# v6566_v1.net
KiCad netlist of a schematic drawn in EAGLE
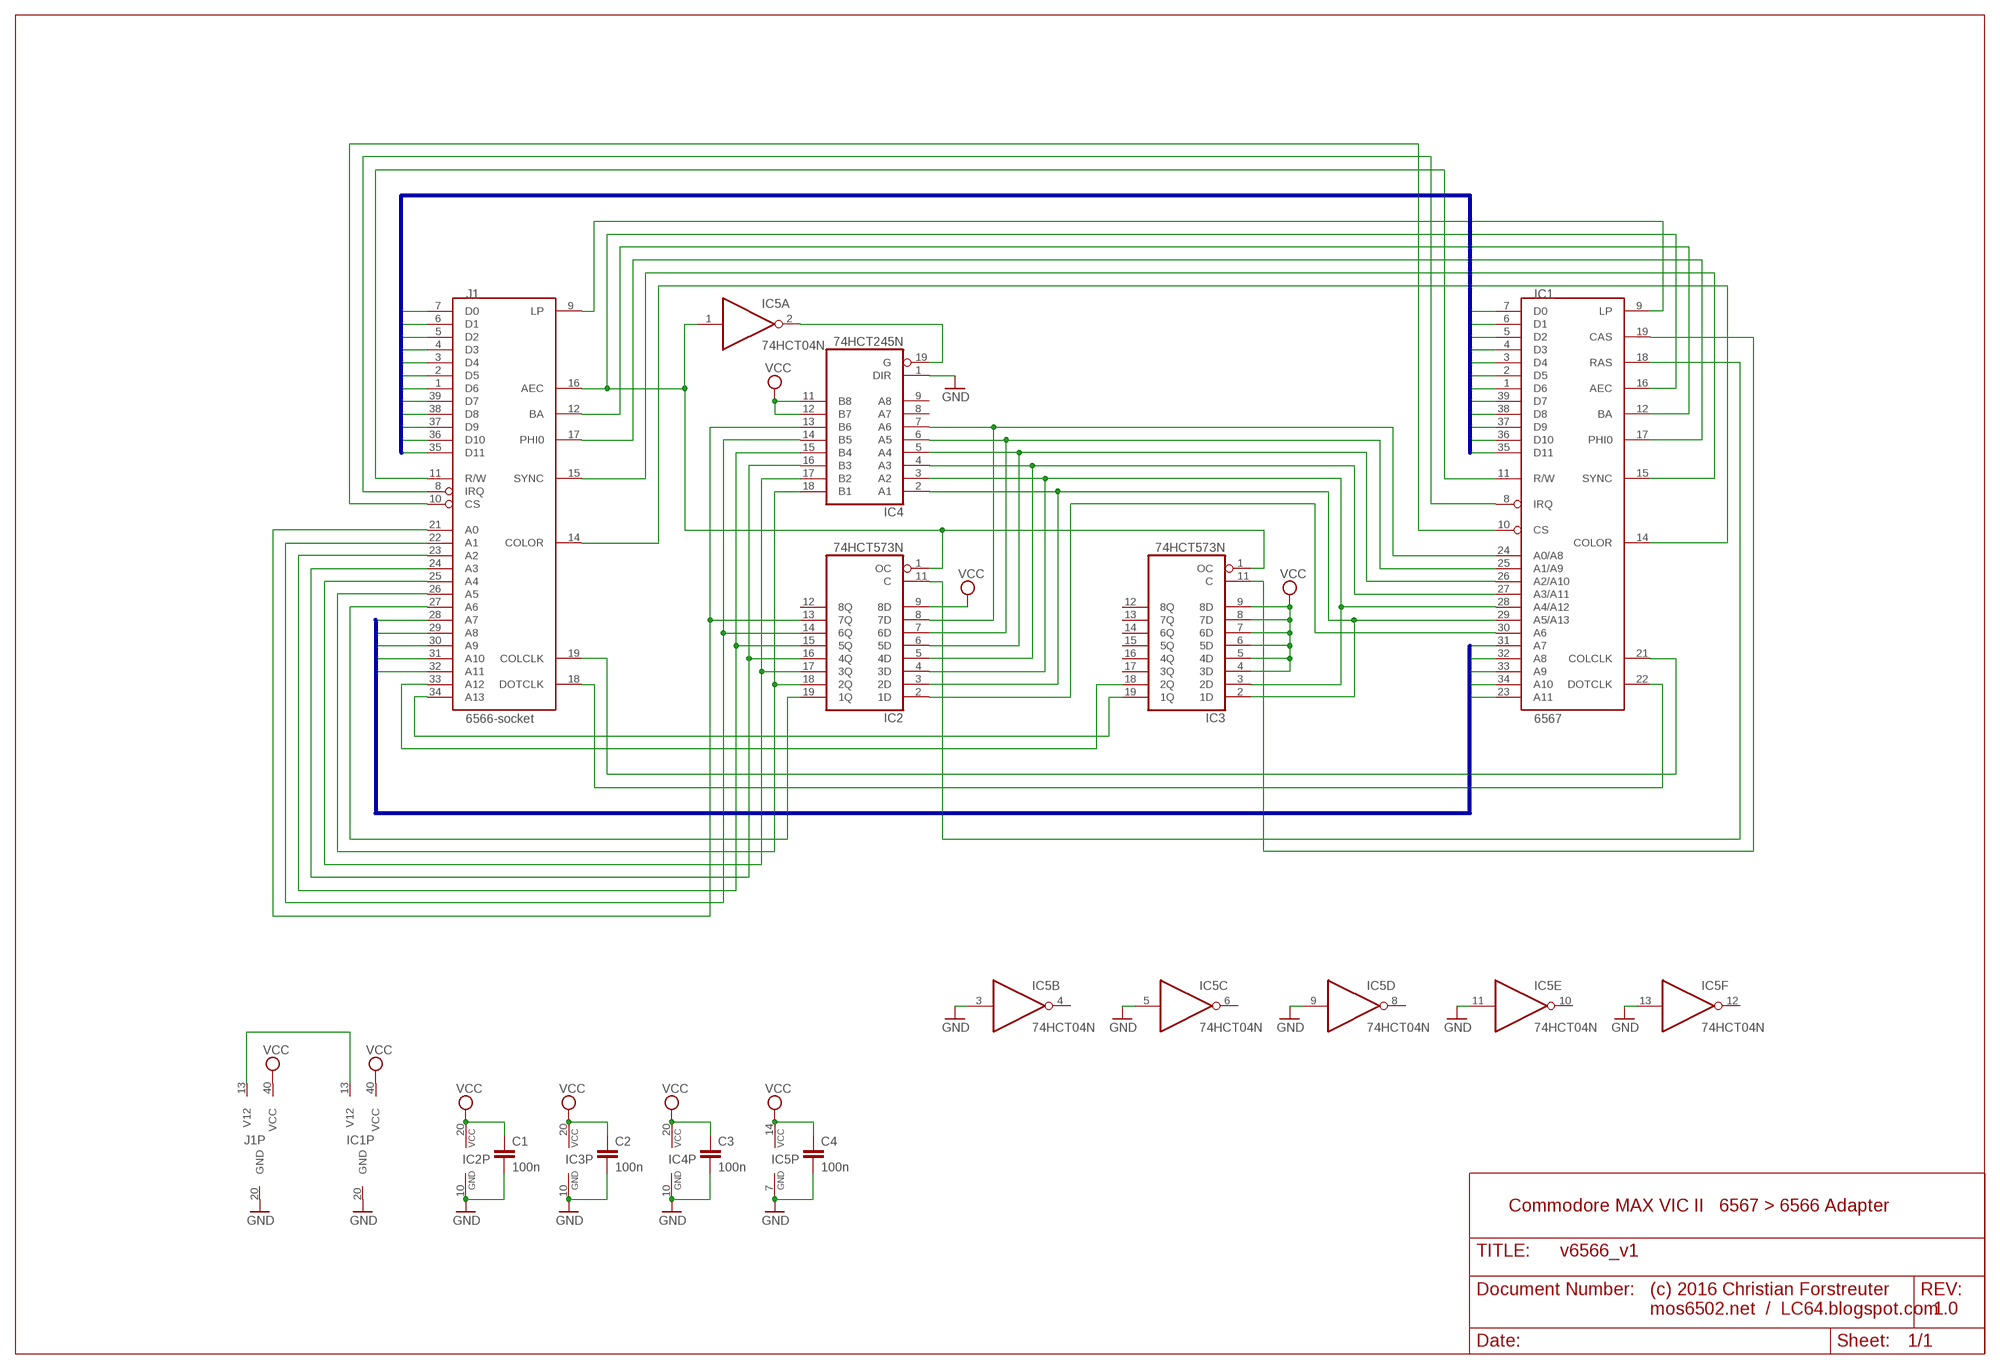
[diagram p0: schematic, sheet 1]

(export (version "E")
  (design (tool "Eeschema 10.0.6"))
  (components
    (comp (ref "C1")
      (value "100n")
      (footprint "eagle-import:_C5MM")
      (libsource (lib "eagle-import") (part "C_CERAMIC_5MM"))
    )
    (comp (ref "C2")
      (value "100n")
      (footprint "eagle-import:_C5MM")
      (libsource (lib "eagle-import") (part "C_CERAMIC_5MM"))
    )
    (comp (ref "C3")
      (value "100n")
      (footprint "eagle-import:_C5MM")
      (libsource (lib "eagle-import") (part "C_CERAMIC_5MM"))
    )
    (comp (ref "C4")
      (value "100n")
      (footprint "eagle-import:_C5MM")
      (libsource (lib "eagle-import") (part "C_CERAMIC_5MM"))
    )
    (comp (ref "IC1")
      (value "6567")
      (footprint "eagle-import:DIP40")
      (libsource (lib "eagle-import") (part "6569"))
    )
    (comp (ref "IC2")
      (value "74HCT573N")
      (footprint "eagle-import:DIL20")
      (libsource (lib "eagle-import") (part "74573NHCT"))
    )
    (comp (ref "IC3")
      (value "74HCT573N")
      (footprint "eagle-import:DIL20")
      (libsource (lib "eagle-import") (part "74573NHCT"))
    )
    (comp (ref "IC4")
      (value "74HCT245N")
      (footprint "eagle-import:DIL20")
      (libsource (lib "eagle-import") (part "74245NHCT"))
    )
    (comp (ref "IC5")
      (value "74HCT04N")
      (footprint "eagle-import:DIL14")
      (libsource (lib "eagle-import") (part "7404NHCT"))
    )
    (comp (ref "J1")
      (value "6566-socket")
      (footprint "eagle-import:DIP40")
      (libsource (lib "eagle-import") (part "6566"))
    )
  )
  (nets
    (net (code "1") (name "/A7") (class "Default")
      (node (ref "IC1") (pin "31") (pinfunction "A7_31") (pintype "bidirectional"))
      (node (ref "J1") (pin "28") (pinfunction "A7_28") (pintype "bidirectional"))
    )
    (net (code "2") (name "/A8") (class "Default")
      (node (ref "IC1") (pin "32") (pinfunction "A8_32") (pintype "input"))
      (node (ref "J1") (pin "29") (pinfunction "A8_29") (pintype "input"))
    )
    (net (code "3") (name "/A9") (class "Default")
      (node (ref "IC1") (pin "33") (pinfunction "A9_33") (pintype "input"))
      (node (ref "J1") (pin "30") (pinfunction "A9_30") (pintype "input"))
    )
    (net (code "4") (name "/A10") (class "Default")
      (node (ref "IC1") (pin "34") (pinfunction "A10_34") (pintype "input"))
      (node (ref "J1") (pin "31") (pinfunction "A10_31") (pintype "input"))
    )
    (net (code "5") (name "/A11") (class "Default")
      (node (ref "IC1") (pin "23") (pinfunction "A11_23") (pintype "input"))
      (node (ref "J1") (pin "32") (pinfunction "A11_32") (pintype "input"))
    )
    (net (code "6") (name "/D0") (class "Default")
      (node (ref "IC1") (pin "7") (pinfunction "D0_7") (pintype "tri_state"))
      (node (ref "J1") (pin "7") (pinfunction "D0_7") (pintype "tri_state"))
    )
    (net (code "7") (name "/D1") (class "Default")
      (node (ref "IC1") (pin "6") (pinfunction "D1_6") (pintype "tri_state"))
      (node (ref "J1") (pin "6") (pinfunction "D1_6") (pintype "tri_state"))
    )
    (net (code "8") (name "/D2") (class "Default")
      (node (ref "IC1") (pin "5") (pinfunction "D2_5") (pintype "tri_state"))
      (node (ref "J1") (pin "5") (pinfunction "D2_5") (pintype "tri_state"))
    )
    (net (code "9") (name "/D3") (class "Default")
      (node (ref "IC1") (pin "4") (pinfunction "D3_4") (pintype "tri_state"))
      (node (ref "J1") (pin "4") (pinfunction "D3_4") (pintype "tri_state"))
    )
    (net (code "10") (name "/D4") (class "Default")
      (node (ref "IC1") (pin "3") (pinfunction "D4_3") (pintype "tri_state"))
      (node (ref "J1") (pin "3") (pinfunction "D4_3") (pintype "tri_state"))
    )
    (net (code "11") (name "/D5") (class "Default")
      (node (ref "IC1") (pin "2") (pinfunction "D5_2") (pintype "tri_state"))
      (node (ref "J1") (pin "2") (pinfunction "D5_2") (pintype "tri_state"))
    )
    (net (code "12") (name "/D6") (class "Default")
      (node (ref "IC1") (pin "1") (pinfunction "D6_1") (pintype "tri_state"))
      (node (ref "J1") (pin "1") (pinfunction "D6_1") (pintype "tri_state"))
    )
    (net (code "13") (name "/D7") (class "Default")
      (node (ref "IC1") (pin "39") (pinfunction "D7_39") (pintype "tri_state"))
      (node (ref "J1") (pin "39") (pinfunction "D7_39") (pintype "tri_state"))
    )
    (net (code "14") (name "/D8") (class "Default")
      (node (ref "IC1") (pin "38") (pinfunction "D8_38") (pintype "tri_state"))
      (node (ref "J1") (pin "38") (pinfunction "D8_38") (pintype "tri_state"))
    )
    (net (code "15") (name "/D9") (class "Default")
      (node (ref "IC1") (pin "37") (pinfunction "D9_37") (pintype "tri_state"))
      (node (ref "J1") (pin "37") (pinfunction "D9_37") (pintype "tri_state"))
    )
    (net (code "16") (name "/D10") (class "Default")
      (node (ref "IC1") (pin "36") (pinfunction "D10_36") (pintype "tri_state"))
      (node (ref "J1") (pin "36") (pinfunction "D10_36") (pintype "tri_state"))
    )
    (net (code "17") (name "/D11") (class "Default")
      (node (ref "IC1") (pin "35") (pinfunction "D11_35") (pintype "tri_state"))
      (node (ref "J1") (pin "35") (pinfunction "D11_35") (pintype "tri_state"))
    )
    (net (code "18") (name "GND") (class "Default")
      (node (ref "C1") (pin "2") (pinfunction "2_2") (pintype "passive"))
      (node (ref "C2") (pin "2") (pinfunction "2_2") (pintype "passive"))
      (node (ref "C3") (pin "2") (pinfunction "2_2") (pintype "passive"))
      (node (ref "C4") (pin "2") (pinfunction "2_2") (pintype "passive"))
      (node (ref "IC1") (pin "20") (pinfunction "GND_20") (pintype "power_in"))
      (node (ref "IC2") (pin "10") (pinfunction "GND_10") (pintype "power_in"))
      (node (ref "IC3") (pin "10") (pinfunction "GND_10") (pintype "power_in"))
      (node (ref "IC4") (pin "1") (pinfunction "DIR_1") (pintype "input"))
      (node (ref "IC4") (pin "10") (pinfunction "GND_10") (pintype "power_in"))
      (node (ref "IC5") (pin "11") (pinfunction "I_11") (pintype "input"))
      (node (ref "IC5") (pin "13") (pinfunction "I_13") (pintype "input"))
      (node (ref "IC5") (pin "3") (pinfunction "I_3") (pintype "input"))
      (node (ref "IC5") (pin "5") (pinfunction "I_5") (pintype "input"))
      (node (ref "IC5") (pin "7") (pinfunction "GND_7") (pintype "power_in"))
      (node (ref "IC5") (pin "9") (pinfunction "I_9") (pintype "input"))
      (node (ref "J1") (pin "20") (pinfunction "GND_20") (pintype "power_in"))
    )
    (net (code "19") (name "Net-(IC1A-A0{slash}A8)") (class "Default")
      (node (ref "IC1") (pin "24") (pinfunction "A0/A8_24") (pintype "bidirectional"))
      (node (ref "IC2") (pin "8") (pinfunction "7D_8") (pintype "input"))
      (node (ref "IC4") (pin "7") (pinfunction "A6_7") (pintype "bidirectional"))
    )
    (net (code "20") (name "Net-(IC1A-A1{slash}A9)") (class "Default")
      (node (ref "IC1") (pin "25") (pinfunction "A1/A9_25") (pintype "bidirectional"))
      (node (ref "IC2") (pin "7") (pinfunction "6D_7") (pintype "input"))
      (node (ref "IC4") (pin "6") (pinfunction "A5_6") (pintype "bidirectional"))
    )
    (net (code "21") (name "Net-(IC1A-A2{slash}A10)") (class "Default")
      (node (ref "IC1") (pin "26") (pinfunction "A2/A10_26") (pintype "bidirectional"))
      (node (ref "IC2") (pin "6") (pinfunction "5D_6") (pintype "input"))
      (node (ref "IC4") (pin "5") (pinfunction "A4_5") (pintype "bidirectional"))
    )
    (net (code "22") (name "Net-(IC1A-A3{slash}A11)") (class "Default")
      (node (ref "IC1") (pin "27") (pinfunction "A3/A11_27") (pintype "bidirectional"))
      (node (ref "IC2") (pin "5") (pinfunction "4D_5") (pintype "input"))
      (node (ref "IC4") (pin "4") (pinfunction "A3_4") (pintype "bidirectional"))
    )
    (net (code "23") (name "Net-(IC1A-A4{slash}A12)") (class "Default")
      (node (ref "IC1") (pin "28") (pinfunction "A4/A12_28") (pintype "bidirectional"))
      (node (ref "IC2") (pin "4") (pinfunction "3D_4") (pintype "input"))
      (node (ref "IC3") (pin "3") (pinfunction "2D_3") (pintype "input"))
      (node (ref "IC4") (pin "3") (pinfunction "A2_3") (pintype "bidirectional"))
    )
    (net (code "24") (name "Net-(IC1A-A5{slash}A13)") (class "Default")
      (node (ref "IC1") (pin "29") (pinfunction "A5/A13_29") (pintype "bidirectional"))
      (node (ref "IC2") (pin "3") (pinfunction "2D_3") (pintype "input"))
      (node (ref "IC3") (pin "2") (pinfunction "1D_2") (pintype "input"))
      (node (ref "IC4") (pin "2") (pinfunction "A1_2") (pintype "bidirectional"))
    )
    (net (code "25") (name "Net-(IC1A-A6)") (class "Default")
      (node (ref "IC1") (pin "30") (pinfunction "A6_30") (pintype "bidirectional"))
      (node (ref "IC2") (pin "2") (pinfunction "1D_2") (pintype "input"))
    )
    (net (code "26") (name "Net-(IC1A-AEC)") (class "Default")
      (node (ref "IC1") (pin "16") (pinfunction "AEC_16") (pintype "output"))
      (node (ref "IC2") (pin "1") (pinfunction "OC_1") (pintype "input"))
      (node (ref "IC3") (pin "1") (pinfunction "OC_1") (pintype "input"))
      (node (ref "IC5") (pin "1") (pinfunction "I_1") (pintype "input"))
      (node (ref "J1") (pin "16") (pinfunction "AEC_16") (pintype "output"))
    )
    (net (code "27") (name "Net-(IC1A-BA)") (class "Default")
      (node (ref "IC1") (pin "12") (pinfunction "BA_12") (pintype "output"))
      (node (ref "J1") (pin "12") (pinfunction "BA_12") (pintype "output"))
    )
    (net (code "28") (name "Net-(IC1A-CAS)") (class "Default")
      (node (ref "IC1") (pin "19") (pinfunction "CAS_19") (pintype "output"))
      (node (ref "IC3") (pin "11") (pinfunction "C_11") (pintype "input"))
    )
    (net (code "29") (name "Net-(IC1A-COLCLK)") (class "Default")
      (node (ref "IC1") (pin "21") (pinfunction "COLCLK_21") (pintype "input"))
      (node (ref "J1") (pin "19") (pinfunction "COLCLK_19") (pintype "input"))
    )
    (net (code "30") (name "Net-(IC1A-COLOR)") (class "Default")
      (node (ref "IC1") (pin "14") (pinfunction "COLOR_14") (pintype "output"))
      (node (ref "J1") (pin "14") (pinfunction "COLOR_14") (pintype "output"))
    )
    (net (code "31") (name "Net-(IC1A-CS)") (class "Default")
      (node (ref "IC1") (pin "10") (pinfunction "CS_10") (pintype "input"))
      (node (ref "J1") (pin "10") (pinfunction "CS_10") (pintype "input"))
    )
    (net (code "32") (name "Net-(IC1A-DOTCLK)") (class "Default")
      (node (ref "IC1") (pin "22") (pinfunction "DOTCLK_22") (pintype "input"))
      (node (ref "J1") (pin "18") (pinfunction "DOTCLK_18") (pintype "input"))
    )
    (net (code "33") (name "Net-(IC1A-IRQ)") (class "Default")
      (node (ref "IC1") (pin "8") (pinfunction "IRQ_8") (pintype "open_collector"))
      (node (ref "J1") (pin "8") (pinfunction "IRQ_8") (pintype "open_collector"))
    )
    (net (code "34") (name "Net-(IC1A-LP)") (class "Default")
      (node (ref "IC1") (pin "9") (pinfunction "LP_9") (pintype "input"))
      (node (ref "J1") (pin "9") (pinfunction "LP_9") (pintype "input"))
    )
    (net (code "35") (name "Net-(IC1A-PHI0)") (class "Default")
      (node (ref "IC1") (pin "17") (pinfunction "PHI0_17") (pintype "output"))
      (node (ref "J1") (pin "17") (pinfunction "PHI0_17") (pintype "output"))
    )
    (net (code "36") (name "Net-(IC1A-RAS)") (class "Default")
      (node (ref "IC1") (pin "18") (pinfunction "RAS_18") (pintype "output"))
      (node (ref "IC2") (pin "11") (pinfunction "C_11") (pintype "input"))
    )
    (net (code "37") (name "Net-(IC1A-R{slash}W)") (class "Default")
      (node (ref "IC1") (pin "11") (pinfunction "R/W_11") (pintype "input"))
      (node (ref "J1") (pin "11") (pinfunction "R/W_11") (pintype "input"))
    )
    (net (code "38") (name "Net-(IC1A-SYNC)") (class "Default")
      (node (ref "IC1") (pin "15") (pinfunction "SYNC_15") (pintype "output"))
      (node (ref "J1") (pin "15") (pinfunction "SYNC_15") (pintype "output"))
    )
    (net (code "39") (name "Net-(IC1B-V12)") (class "Default")
      (node (ref "IC1") (pin "13") (pinfunction "V12_13") (pintype "power_in"))
      (node (ref "J1") (pin "13") (pinfunction "V12_13") (pintype "power_in"))
    )
    (net (code "40") (name "Net-(IC2A-1Q)") (class "Default")
      (node (ref "IC2") (pin "19") (pinfunction "1Q_19") (pintype "tri_state"))
      (node (ref "J1") (pin "27") (pinfunction "A6_27") (pintype "bidirectional"))
    )
    (net (code "41") (name "Net-(IC2A-2Q)") (class "Default")
      (node (ref "IC2") (pin "18") (pinfunction "2Q_18") (pintype "tri_state"))
      (node (ref "IC4") (pin "18") (pinfunction "B1_18") (pintype "bidirectional"))
      (node (ref "J1") (pin "26") (pinfunction "A5_26") (pintype "bidirectional"))
    )
    (net (code "42") (name "Net-(IC2A-3Q)") (class "Default")
      (node (ref "IC2") (pin "17") (pinfunction "3Q_17") (pintype "tri_state"))
      (node (ref "IC4") (pin "17") (pinfunction "B2_17") (pintype "bidirectional"))
      (node (ref "J1") (pin "25") (pinfunction "A4_25") (pintype "bidirectional"))
    )
    (net (code "43") (name "Net-(IC2A-4Q)") (class "Default")
      (node (ref "IC2") (pin "16") (pinfunction "4Q_16") (pintype "tri_state"))
      (node (ref "IC4") (pin "16") (pinfunction "B3_16") (pintype "bidirectional"))
      (node (ref "J1") (pin "24") (pinfunction "A3_24") (pintype "bidirectional"))
    )
    (net (code "44") (name "Net-(IC2A-5Q)") (class "Default")
      (node (ref "IC2") (pin "15") (pinfunction "5Q_15") (pintype "tri_state"))
      (node (ref "IC4") (pin "15") (pinfunction "B4_15") (pintype "bidirectional"))
      (node (ref "J1") (pin "23") (pinfunction "A2_23") (pintype "bidirectional"))
    )
    (net (code "45") (name "Net-(IC2A-6Q)") (class "Default")
      (node (ref "IC2") (pin "14") (pinfunction "6Q_14") (pintype "tri_state"))
      (node (ref "IC4") (pin "14") (pinfunction "B5_14") (pintype "bidirectional"))
      (node (ref "J1") (pin "22") (pinfunction "A1_22") (pintype "bidirectional"))
    )
    (net (code "46") (name "Net-(IC2A-7Q)") (class "Default")
      (node (ref "IC2") (pin "13") (pinfunction "7Q_13") (pintype "tri_state"))
      (node (ref "IC4") (pin "13") (pinfunction "B6_13") (pintype "bidirectional"))
      (node (ref "J1") (pin "21") (pinfunction "A0_21") (pintype "bidirectional"))
    )
    (net (code "47") (name "Net-(IC3A-1Q)") (class "Default")
      (node (ref "IC3") (pin "19") (pinfunction "1Q_19") (pintype "tri_state"))
      (node (ref "J1") (pin "34") (pinfunction "A13_34") (pintype "input"))
    )
    (net (code "48") (name "Net-(IC3A-2Q)") (class "Default")
      (node (ref "IC3") (pin "18") (pinfunction "2Q_18") (pintype "tri_state"))
      (node (ref "J1") (pin "33") (pinfunction "A12_33") (pintype "input"))
    )
    (net (code "49") (name "Net-(IC4A-G)") (class "Default")
      (node (ref "IC4") (pin "19") (pinfunction "G_19") (pintype "input"))
      (node (ref "IC5") (pin "2") (pinfunction "O_2") (pintype "output"))
    )
    (net (code "50") (name "VCC") (class "Default")
      (node (ref "C1") (pin "1") (pinfunction "1_1") (pintype "passive"))
      (node (ref "C2") (pin "1") (pinfunction "1_1") (pintype "passive"))
      (node (ref "C3") (pin "1") (pinfunction "1_1") (pintype "passive"))
      (node (ref "C4") (pin "1") (pinfunction "1_1") (pintype "passive"))
      (node (ref "IC1") (pin "40") (pinfunction "VCC_40") (pintype "power_in"))
      (node (ref "IC2") (pin "20") (pinfunction "VCC_20") (pintype "power_in"))
      (node (ref "IC2") (pin "9") (pinfunction "8D_9") (pintype "input"))
      (node (ref "IC3") (pin "20") (pinfunction "VCC_20") (pintype "power_in"))
      (node (ref "IC3") (pin "4") (pinfunction "3D_4") (pintype "input"))
      (node (ref "IC3") (pin "5") (pinfunction "4D_5") (pintype "input"))
      (node (ref "IC3") (pin "6") (pinfunction "5D_6") (pintype "input"))
      (node (ref "IC3") (pin "7") (pinfunction "6D_7") (pintype "input"))
      (node (ref "IC3") (pin "8") (pinfunction "7D_8") (pintype "input"))
      (node (ref "IC3") (pin "9") (pinfunction "8D_9") (pintype "input"))
      (node (ref "IC4") (pin "11") (pinfunction "B8_11") (pintype "bidirectional"))
      (node (ref "IC4") (pin "12") (pinfunction "B7_12") (pintype "bidirectional"))
      (node (ref "IC4") (pin "20") (pinfunction "VCC_20") (pintype "power_in"))
      (node (ref "IC5") (pin "14") (pinfunction "VCC_14") (pintype "power_in"))
      (node (ref "J1") (pin "40") (pinfunction "VCC_40") (pintype "power_in"))
    )
    (net (code "51") (name "unconnected-(IC2A-8Q-Pad12)") (class "Default")
      (node (ref "IC2") (pin "12") (pinfunction "8Q_12") (pintype "tri_state"))
    )
    (net (code "52") (name "unconnected-(IC3A-3Q-Pad17)") (class "Default")
      (node (ref "IC3") (pin "17") (pinfunction "3Q_17") (pintype "tri_state"))
    )
    (net (code "53") (name "unconnected-(IC3A-4Q-Pad16)") (class "Default")
      (node (ref "IC3") (pin "16") (pinfunction "4Q_16") (pintype "tri_state"))
    )
    (net (code "54") (name "unconnected-(IC3A-5Q-Pad15)") (class "Default")
      (node (ref "IC3") (pin "15") (pinfunction "5Q_15") (pintype "tri_state"))
    )
    (net (code "55") (name "unconnected-(IC3A-6Q-Pad14)") (class "Default")
      (node (ref "IC3") (pin "14") (pinfunction "6Q_14") (pintype "tri_state"))
    )
    (net (code "56") (name "unconnected-(IC3A-7Q-Pad13)") (class "Default")
      (node (ref "IC3") (pin "13") (pinfunction "7Q_13") (pintype "tri_state"))
    )
    (net (code "57") (name "unconnected-(IC3A-8Q-Pad12)") (class "Default")
      (node (ref "IC3") (pin "12") (pinfunction "8Q_12") (pintype "tri_state"))
    )
    (net (code "58") (name "unconnected-(IC4A-A7-Pad8)") (class "Default")
      (node (ref "IC4") (pin "8") (pinfunction "A7_8") (pintype "bidirectional"))
    )
    (net (code "59") (name "unconnected-(IC4A-A8-Pad9)") (class "Default")
      (node (ref "IC4") (pin "9") (pinfunction "A8_9") (pintype "bidirectional"))
    )
    (net (code "60") (name "unconnected-(IC5B-O-Pad4)") (class "Default")
      (node (ref "IC5") (pin "4") (pinfunction "O_4") (pintype "output"))
    )
    (net (code "61") (name "unconnected-(IC5C-O-Pad6)") (class "Default")
      (node (ref "IC5") (pin "6") (pinfunction "O_6") (pintype "output"))
    )
    (net (code "62") (name "unconnected-(IC5D-O-Pad8)") (class "Default")
      (node (ref "IC5") (pin "8") (pinfunction "O_8") (pintype "output"))
    )
    (net (code "63") (name "unconnected-(IC5E-O-Pad10)") (class "Default")
      (node (ref "IC5") (pin "10") (pinfunction "O_10") (pintype "output"))
    )
    (net (code "64") (name "unconnected-(IC5F-O-Pad12)") (class "Default")
      (node (ref "IC5") (pin "12") (pinfunction "O_12") (pintype "output"))
    )
  )
)
